# Mint_-_SCH_2025-02-01.net
KiCad netlist of a schematic drawn in EasyEDA
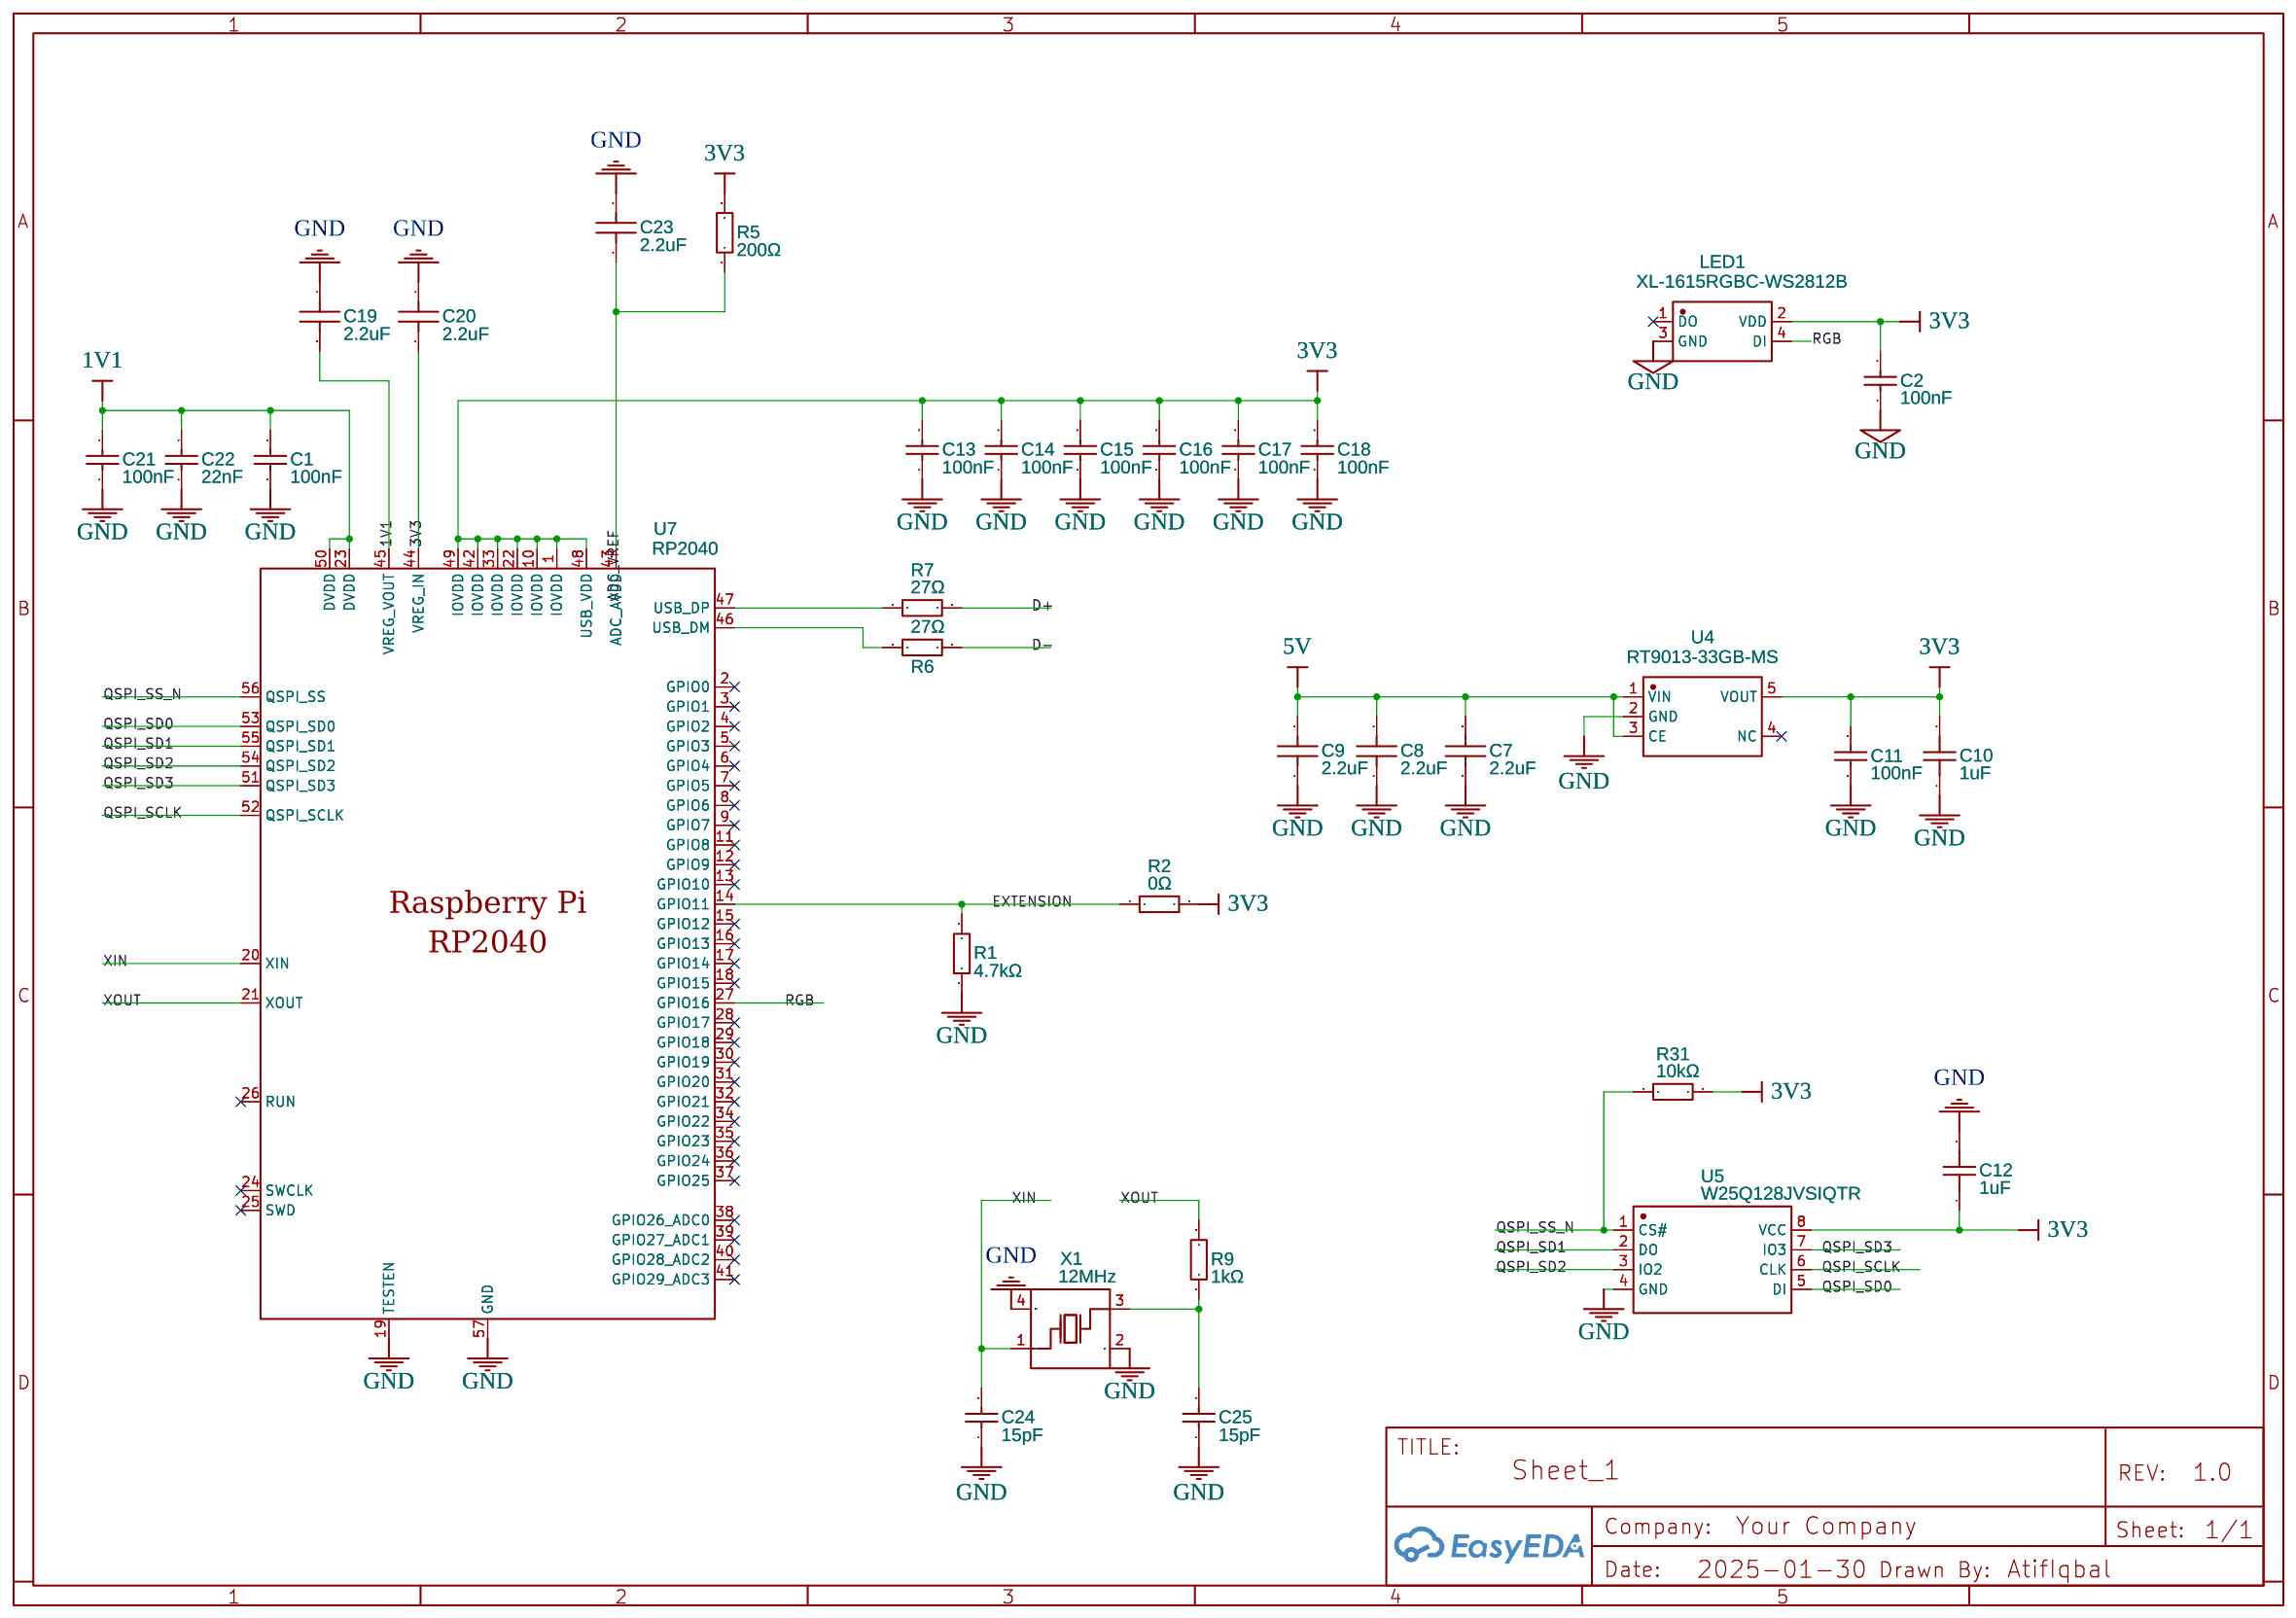
[diagram p0: schematic sheet]

(export (version "E")
  (design (tool "Eeschema 10.0.6"))
  (components
    (comp (ref "C1")
      (value "100nF")
      (fields
        (field (name "Manufacturer Part") "CL05B104KO5NNNC")
        (field (name "Manufacturer") "SAMSUNG(三星)")
      )
      (libsource (lib "") (part "CL05B104KO5NNNC"))
    )
    (comp (ref "C2")
      (value "100nF")
      (fields
        (field (name "Manufacturer Part") "CL05B104KO5NNNC")
        (field (name "Manufacturer") "SAMSUNG(三星)")
      )
      (libsource (lib "") (part "CL05B104KO5NNNC"))
    )
    (comp (ref "C7")
      (value "2.2uF")
      (fields
        (field (name "Manufacturer Part") "CL05A225MQ5NSNC")
        (field (name "Manufacturer") "SAMSUNG(三星)")
      )
      (libsource (lib "") (part "CL05A225MQ5NSNC"))
    )
    (comp (ref "C8")
      (value "2.2uF")
      (fields
        (field (name "Manufacturer Part") "CL05A225MQ5NSNC")
        (field (name "Manufacturer") "SAMSUNG(三星)")
      )
      (libsource (lib "") (part "CL05A225MQ5NSNC"))
    )
    (comp (ref "C9")
      (value "2.2uF")
      (fields
        (field (name "Manufacturer Part") "CL05A225MQ5NSNC")
        (field (name "Manufacturer") "SAMSUNG(三星)")
      )
      (libsource (lib "") (part "CL05A225MQ5NSNC"))
    )
    (comp (ref "C10")
      (value "1uF")
      (fields
        (field (name "Manufacturer Part") "CL05A105KA5NQNC")
        (field (name "Manufacturer") "SAMSUNG(三星)")
      )
      (libsource (lib "") (part "CL05A105KA5NQNC"))
    )
    (comp (ref "C11")
      (value "100nF")
      (fields
        (field (name "Manufacturer Part") "CL05B104KO5NNNC")
        (field (name "Manufacturer") "SAMSUNG(三星)")
      )
      (libsource (lib "") (part "CL05B104KO5NNNC"))
    )
    (comp (ref "C12")
      (value "1uF")
      (fields
        (field (name "Manufacturer Part") "CL05A105KA5NQNC")
        (field (name "Manufacturer") "SAMSUNG(三星)")
      )
      (libsource (lib "") (part "CL05A105KA5NQNC"))
    )
    (comp (ref "C13")
      (value "100nF")
      (fields
        (field (name "Manufacturer Part") "CL05B104KO5NNNC")
        (field (name "Manufacturer") "SAMSUNG(三星)")
      )
      (libsource (lib "") (part "CL05B104KO5NNNC"))
    )
    (comp (ref "C14")
      (value "100nF")
      (fields
        (field (name "Manufacturer Part") "CL05B104KO5NNNC")
        (field (name "Manufacturer") "SAMSUNG(三星)")
      )
      (libsource (lib "") (part "CL05B104KO5NNNC"))
    )
    (comp (ref "C15")
      (value "100nF")
      (fields
        (field (name "Manufacturer Part") "CL05B104KO5NNNC")
        (field (name "Manufacturer") "SAMSUNG(三星)")
      )
      (libsource (lib "") (part "CL05B104KO5NNNC"))
    )
    (comp (ref "C16")
      (value "100nF")
      (fields
        (field (name "Manufacturer Part") "CL05B104KO5NNNC")
        (field (name "Manufacturer") "SAMSUNG(三星)")
      )
      (libsource (lib "") (part "CL05B104KO5NNNC"))
    )
    (comp (ref "C17")
      (value "100nF")
      (fields
        (field (name "Manufacturer Part") "CL05B104KO5NNNC")
        (field (name "Manufacturer") "SAMSUNG(三星)")
      )
      (libsource (lib "") (part "CL05B104KO5NNNC"))
    )
    (comp (ref "C18")
      (value "100nF")
      (fields
        (field (name "Manufacturer Part") "CL05B104KO5NNNC")
        (field (name "Manufacturer") "SAMSUNG(三星)")
      )
      (libsource (lib "") (part "CL05B104KO5NNNC"))
    )
    (comp (ref "C19")
      (value "2.2uF")
      (fields
        (field (name "Manufacturer Part") "CL05A225MQ5NSNC")
        (field (name "Manufacturer") "SAMSUNG(三星)")
      )
      (libsource (lib "") (part "CL05A225MQ5NSNC_1"))
    )
    (comp (ref "C20")
      (value "2.2uF")
      (fields
        (field (name "Manufacturer Part") "CL05A225MQ5NSNC")
        (field (name "Manufacturer") "SAMSUNG(三星)")
      )
      (libsource (lib "") (part "CL05A225MQ5NSNC_1"))
    )
    (comp (ref "C21")
      (value "100nF")
      (fields
        (field (name "Manufacturer Part") "CL05B104KO5NNNC")
        (field (name "Manufacturer") "SAMSUNG(三星)")
      )
      (libsource (lib "") (part "CL05B104KO5NNNC"))
    )
    (comp (ref "C22")
      (value "22nF")
      (fields (field (name "Manufacturer Part") "0402B223K500NT") (field (name "Manufacturer") "FH(风华)"))
      (libsource (lib "") (part "0402B223K500NT"))
    )
    (comp (ref "C23")
      (value "2.2uF")
      (fields
        (field (name "Manufacturer Part") "CL05A225MQ5NSNC")
        (field (name "Manufacturer") "SAMSUNG(三星)")
      )
      (libsource (lib "") (part "CL05A225MQ5NSNC"))
    )
    (comp (ref "C24")
      (value "15pF")
      (fields (field (name "Manufacturer Part") "0402CG150J500NT") (field (name "Manufacturer") "FH(风华)"))
      (libsource (lib "") (part "0402CG150J500NT"))
    )
    (comp (ref "C25")
      (value "15pF")
      (fields (field (name "Manufacturer Part") "0402CG150J500NT") (field (name "Manufacturer") "FH(风华)"))
      (libsource (lib "") (part "0402CG150J500NT"))
    )
    (comp (ref "LED1")
      (value "XL-1615RGBC-WS2812B")
      (fields (field (name "Manufacturer") "XINGLIGHT(成兴光)"))
      (libsource (lib "") (part "XL-1615RGBC-WS2812B"))
    )
    (comp (ref "R1")
      (value "4.7kΩ")
      (fields
        (field (name "Manufacturer Part") "0402WGF4701TCE")
        (field (name "Manufacturer") "UNI-ROYAL(厚声)")
      )
      (libsource (lib "") (part "0402WGF4701TCE"))
    )
    (comp (ref "R2")
      (value "0Ω")
      (fields
        (field (name "Manufacturer Part") "0402WGF0000TCE")
        (field (name "Manufacturer") "UNI-ROYAL(厚声)")
      )
      (libsource (lib "") (part "0402WGF0000TCE"))
    )
    (comp (ref "R5")
      (value "200Ω")
      (fields
        (field (name "Manufacturer Part") "0402WGF2000TCE")
        (field (name "Manufacturer") "UNI-ROYAL(厚声)")
      )
      (libsource (lib "") (part "0402WGF2000TCE"))
    )
    (comp (ref "R6")
      (value "27Ω")
      (fields
        (field (name "Manufacturer Part") "0402WGJ0270TCE")
        (field (name "Manufacturer") "UNI-ROYAL(厚声)")
      )
      (libsource (lib "") (part "0402WGJ0270TCE"))
    )
    (comp (ref "R7")
      (value "27Ω")
      (fields
        (field (name "Manufacturer Part") "0402WGJ0270TCE")
        (field (name "Manufacturer") "UNI-ROYAL(厚声)")
      )
      (libsource (lib "") (part "0402WGJ0270TCE"))
    )
    (comp (ref "R9")
      (value "1kΩ")
      (fields
        (field (name "Manufacturer Part") "0402WGF1001TCE")
        (field (name "Manufacturer") "UNI-ROYAL(厚声)")
      )
      (libsource (lib "") (part "0402WGF1001TCE"))
    )
    (comp (ref "R31")
      (value "10kΩ")
      (fields (field (name "Manufacturer Part") "0402WGF1002TCE") (field (name "Manufacturer") "UniOhm"))
      (libsource (lib "") (part "0402WGF1002TCE"))
    )
    (comp (ref "U4")
      (value "RT9013-33GB-MS")
      (fields (field (name "Manufacturer") "MSKSEMI(美森科)"))
      (libsource (lib "") (part "RT9013-33GB-MS"))
    )
    (comp (ref "U5")
      (value "W25Q128JVSIQTR")
      (fields (field (name "Manufacturer Part") "W25Q128JVSIQ") (field (name "Manufacturer") "WINBOND(华邦)"))
      (libsource (lib "") (part "W25Q128JVSIQTR"))
    )
    (comp (ref "U7")
      (value "RP2040")
      (fields (field (name "Manufacturer") "Raspberry Pi(树莓派)"))
      (libsource (lib "") (part "RP2040"))
    )
    (comp (ref "X1")
      (value "12MHz")
      (fields (field (name "Manufacturer") "TAE(雅晶鑫)"))
      (libsource (lib "") (part "SMD-3225_4P12M12PF10PPM"))
    )
  )
  (nets
    (net (code "1") (name "/ADC_VREF") (class "Default")
      (node (ref "C23") (pin "1") (pinfunction "1_1") (pintype "unspecified"))
      (node (ref "R5") (pin "1") (pinfunction "1_1") (pintype "input"))
      (node (ref "U7") (pin "43") (pinfunction "ADC_AVDD_43") (pintype "bidirectional"))
    )
    (net (code "2") (name "/D+") (class "Default")
      (node (ref "R7") (pin "2") (pinfunction "2_2") (pintype "input"))
    )
    (net (code "3") (name "/D-") (class "Default")
      (node (ref "R6") (pin "2") (pinfunction "2_2") (pintype "input"))
    )
    (net (code "4") (name "/EXTENSION") (class "Default")
      (node (ref "R1") (pin "2") (pinfunction "2_2") (pintype "input"))
      (node (ref "R2") (pin "1") (pinfunction "1_1") (pintype "input"))
      (node (ref "U7") (pin "14") (pinfunction "GPIO11_14") (pintype "bidirectional"))
    )
    (net (code "5") (name "/QSPI_SCLK") (class "Default")
      (node (ref "U5") (pin "6") (pinfunction "CLK_6") (pintype "unspecified"))
      (node (ref "U7") (pin "52") (pinfunction "QSPI_SCLK_52") (pintype "output"))
    )
    (net (code "6") (name "/QSPI_SD0") (class "Default")
      (node (ref "U5") (pin "5") (pinfunction "DI_5") (pintype "unspecified"))
      (node (ref "U7") (pin "53") (pinfunction "QSPI_SD0_53") (pintype "bidirectional"))
    )
    (net (code "7") (name "/QSPI_SD1") (class "Default")
      (node (ref "U5") (pin "2") (pinfunction "DO_2") (pintype "unspecified"))
      (node (ref "U7") (pin "55") (pinfunction "QSPI_SD1_55") (pintype "bidirectional"))
    )
    (net (code "8") (name "/QSPI_SD2") (class "Default")
      (node (ref "U5") (pin "3") (pinfunction "IO2_3") (pintype "unspecified"))
      (node (ref "U7") (pin "54") (pinfunction "QSPI_SD2_54") (pintype "bidirectional"))
    )
    (net (code "9") (name "/QSPI_SD3") (class "Default")
      (node (ref "U5") (pin "7") (pinfunction "IO3_7") (pintype "unspecified"))
      (node (ref "U7") (pin "51") (pinfunction "QSPI_SD3_51") (pintype "bidirectional"))
    )
    (net (code "10") (name "/QSPI_SS_N") (class "Default")
      (node (ref "R31") (pin "1") (pinfunction "1_1") (pintype "input"))
      (node (ref "U5") (pin "1") (pinfunction "CS#_1") (pintype "unspecified"))
      (node (ref "U7") (pin "56") (pinfunction "QSPI_SS_56") (pintype "bidirectional"))
    )
    (net (code "11") (name "/RGB") (class "Default")
      (node (ref "LED1") (pin "4") (pinfunction "DI_4") (pintype "unspecified"))
      (node (ref "U7") (pin "27") (pinfunction "GPIO16_27") (pintype "bidirectional"))
    )
    (net (code "12") (name "/XIN") (class "Default")
      (node (ref "C24") (pin "2") (pinfunction "2_2") (pintype "input"))
      (node (ref "U7") (pin "20") (pinfunction "XIN_20") (pintype "input"))
      (node (ref "X1") (pin "1") (pinfunction "OSC1_1") (pintype "unspecified"))
    )
    (net (code "13") (name "/XOUT") (class "Default")
      (node (ref "R9") (pin "2") (pinfunction "2_2") (pintype "input"))
      (node (ref "U7") (pin "21") (pinfunction "XOUT_21") (pintype "unspecified"))
    )
    (net (code "14") (name "1V1") (class "Default")
      (node (ref "C1") (pin "2") (pinfunction "2_2") (pintype "input"))
      (node (ref "C19") (pin "2") (pinfunction "2_2") (pintype "unspecified"))
      (node (ref "C21") (pin "2") (pinfunction "2_2") (pintype "input"))
      (node (ref "C22") (pin "1") (pinfunction "1_1") (pintype "input"))
      (node (ref "U7") (pin "23") (pinfunction "DVDD_23") (pintype "bidirectional"))
      (node (ref "U7") (pin "45") (pinfunction "VREG_VOUT_45") (pintype "bidirectional"))
      (node (ref "U7") (pin "50") (pinfunction "DVDD_50") (pintype "bidirectional"))
    )
    (net (code "15") (name "3V3") (class "Default")
      (node (ref "C10") (pin "2") (pinfunction "2_2") (pintype "unspecified"))
      (node (ref "C11") (pin "2") (pinfunction "2_2") (pintype "input"))
      (node (ref "C12") (pin "1") (pinfunction "1_1") (pintype "unspecified"))
      (node (ref "C13") (pin "2") (pinfunction "2_2") (pintype "input"))
      (node (ref "C14") (pin "2") (pinfunction "2_2") (pintype "input"))
      (node (ref "C15") (pin "2") (pinfunction "2_2") (pintype "input"))
      (node (ref "C16") (pin "2") (pinfunction "2_2") (pintype "input"))
      (node (ref "C17") (pin "2") (pinfunction "2_2") (pintype "input"))
      (node (ref "C18") (pin "2") (pinfunction "2_2") (pintype "input"))
      (node (ref "C2") (pin "2") (pinfunction "2_2") (pintype "input"))
      (node (ref "C20") (pin "2") (pinfunction "2_2") (pintype "unspecified"))
      (node (ref "LED1") (pin "2") (pinfunction "VDD_2") (pintype "unspecified"))
      (node (ref "R2") (pin "2") (pinfunction "2_2") (pintype "input"))
      (node (ref "R31") (pin "2") (pinfunction "2_2") (pintype "input"))
      (node (ref "R5") (pin "2") (pinfunction "2_2") (pintype "input"))
      (node (ref "U4") (pin "5") (pinfunction "VOUT_5") (pintype "unspecified"))
      (node (ref "U5") (pin "8") (pinfunction "VCC_8") (pintype "unspecified"))
      (node (ref "U7") (pin "1") (pinfunction "IOVDD_1") (pintype "bidirectional"))
      (node (ref "U7") (pin "10") (pinfunction "IOVDD_10") (pintype "bidirectional"))
      (node (ref "U7") (pin "22") (pinfunction "IOVDD_22") (pintype "bidirectional"))
      (node (ref "U7") (pin "33") (pinfunction "IOVDD_33") (pintype "bidirectional"))
      (node (ref "U7") (pin "42") (pinfunction "IOVDD_42") (pintype "bidirectional"))
      (node (ref "U7") (pin "44") (pinfunction "VREG_IN_44") (pintype "bidirectional"))
      (node (ref "U7") (pin "48") (pinfunction "USB_VDD_48") (pintype "bidirectional"))
      (node (ref "U7") (pin "49") (pinfunction "IOVDD_49") (pintype "bidirectional"))
    )
    (net (code "16") (name "5V") (class "Default")
      (node (ref "C7") (pin "2") (pinfunction "2_2") (pintype "unspecified"))
      (node (ref "C8") (pin "2") (pinfunction "2_2") (pintype "unspecified"))
      (node (ref "C9") (pin "2") (pinfunction "2_2") (pintype "unspecified"))
      (node (ref "U4") (pin "1") (pinfunction "VIN_1") (pintype "unspecified"))
      (node (ref "U4") (pin "3") (pinfunction "CE_3") (pintype "unspecified"))
    )
    (net (code "17") (name "GND") (class "Default")
      (node (ref "C1") (pin "1") (pinfunction "1_1") (pintype "input"))
      (node (ref "C10") (pin "1") (pinfunction "1_1") (pintype "unspecified"))
      (node (ref "C11") (pin "1") (pinfunction "1_1") (pintype "input"))
      (node (ref "C12") (pin "2") (pinfunction "2_2") (pintype "unspecified"))
      (node (ref "C13") (pin "1") (pinfunction "1_1") (pintype "input"))
      (node (ref "C14") (pin "1") (pinfunction "1_1") (pintype "input"))
      (node (ref "C15") (pin "1") (pinfunction "1_1") (pintype "input"))
      (node (ref "C16") (pin "1") (pinfunction "1_1") (pintype "input"))
      (node (ref "C17") (pin "1") (pinfunction "1_1") (pintype "input"))
      (node (ref "C18") (pin "1") (pinfunction "1_1") (pintype "input"))
      (node (ref "C19") (pin "1") (pinfunction "1_1") (pintype "unspecified"))
      (node (ref "C2") (pin "1") (pinfunction "1_1") (pintype "input"))
      (node (ref "C20") (pin "1") (pinfunction "1_1") (pintype "unspecified"))
      (node (ref "C21") (pin "1") (pinfunction "1_1") (pintype "input"))
      (node (ref "C22") (pin "2") (pinfunction "2_2") (pintype "input"))
      (node (ref "C23") (pin "2") (pinfunction "2_2") (pintype "unspecified"))
      (node (ref "C24") (pin "1") (pinfunction "1_1") (pintype "input"))
      (node (ref "C25") (pin "1") (pinfunction "1_1") (pintype "input"))
      (node (ref "C7") (pin "1") (pinfunction "1_1") (pintype "unspecified"))
      (node (ref "C8") (pin "1") (pinfunction "1_1") (pintype "unspecified"))
      (node (ref "C9") (pin "1") (pinfunction "1_1") (pintype "unspecified"))
      (node (ref "LED1") (pin "3") (pinfunction "GND_3") (pintype "unspecified"))
      (node (ref "R1") (pin "1") (pinfunction "1_1") (pintype "input"))
      (node (ref "U4") (pin "2") (pinfunction "GND_2") (pintype "unspecified"))
      (node (ref "U5") (pin "4") (pinfunction "GND_4") (pintype "unspecified"))
      (node (ref "U7") (pin "19") (pinfunction "TESTEN_19") (pintype "unspecified"))
      (node (ref "U7") (pin "57") (pinfunction "GND_57") (pintype "bidirectional"))
      (node (ref "X1") (pin "2") (pinfunction "GND_2") (pintype "unspecified"))
      (node (ref "X1") (pin "4") (pinfunction "GND_4") (pintype "unspecified"))
    )
    (net (code "18") (name "Net-(U7-USB_DM)") (class "Default")
      (node (ref "R6") (pin "1") (pinfunction "1_1") (pintype "input"))
      (node (ref "U7") (pin "46") (pinfunction "USB_DM_46") (pintype "bidirectional"))
    )
    (net (code "19") (name "Net-(U7-USB_DP)") (class "Default")
      (node (ref "R7") (pin "1") (pinfunction "1_1") (pintype "input"))
      (node (ref "U7") (pin "47") (pinfunction "USB_DP_47") (pintype "bidirectional"))
    )
    (net (code "20") (name "Net-(X1-OSC2)") (class "Default")
      (node (ref "C25") (pin "2") (pinfunction "2_2") (pintype "input"))
      (node (ref "R9") (pin "1") (pinfunction "1_1") (pintype "input"))
      (node (ref "X1") (pin "3") (pinfunction "OSC2_3") (pintype "unspecified"))
    )
    (net (code "21") (name "unconnected-(LED1-DO-Pad1)") (class "Default")
      (node (ref "LED1") (pin "1") (pinfunction "DO_1") (pintype "unspecified+no_connect"))
    )
    (net (code "22") (name "unconnected-(U4-NC-Pad4)") (class "Default")
      (node (ref "U4") (pin "4") (pinfunction "NC_4") (pintype "unspecified+no_connect"))
    )
    (net (code "23") (name "unconnected-(U7-GPIO0-Pad2)") (class "Default")
      (node (ref "U7") (pin "2") (pinfunction "GPIO0_2") (pintype "bidirectional+no_connect"))
    )
    (net (code "24") (name "unconnected-(U7-GPIO1-Pad3)") (class "Default")
      (node (ref "U7") (pin "3") (pinfunction "GPIO1_3") (pintype "bidirectional+no_connect"))
    )
    (net (code "25") (name "unconnected-(U7-GPIO2-Pad4)") (class "Default")
      (node (ref "U7") (pin "4") (pinfunction "GPIO2_4") (pintype "bidirectional+no_connect"))
    )
    (net (code "26") (name "unconnected-(U7-GPIO3-Pad5)") (class "Default")
      (node (ref "U7") (pin "5") (pinfunction "GPIO3_5") (pintype "bidirectional+no_connect"))
    )
    (net (code "27") (name "unconnected-(U7-GPIO4-Pad6)") (class "Default")
      (node (ref "U7") (pin "6") (pinfunction "GPIO4_6") (pintype "bidirectional+no_connect"))
    )
    (net (code "28") (name "unconnected-(U7-GPIO5-Pad7)") (class "Default")
      (node (ref "U7") (pin "7") (pinfunction "GPIO5_7") (pintype "bidirectional+no_connect"))
    )
    (net (code "29") (name "unconnected-(U7-GPIO6-Pad8)") (class "Default")
      (node (ref "U7") (pin "8") (pinfunction "GPIO6_8") (pintype "bidirectional+no_connect"))
    )
    (net (code "30") (name "unconnected-(U7-GPIO7-Pad9)") (class "Default")
      (node (ref "U7") (pin "9") (pinfunction "GPIO7_9") (pintype "bidirectional+no_connect"))
    )
    (net (code "31") (name "unconnected-(U7-GPIO8-Pad11)") (class "Default")
      (node (ref "U7") (pin "11") (pinfunction "GPIO8_11") (pintype "bidirectional+no_connect"))
    )
    (net (code "32") (name "unconnected-(U7-GPIO9-Pad12)") (class "Default")
      (node (ref "U7") (pin "12") (pinfunction "GPIO9_12") (pintype "bidirectional+no_connect"))
    )
    (net (code "33") (name "unconnected-(U7-GPIO10-Pad13)") (class "Default")
      (node (ref "U7") (pin "13") (pinfunction "GPIO10_13") (pintype "bidirectional+no_connect"))
    )
    (net (code "34") (name "unconnected-(U7-GPIO12-Pad15)") (class "Default")
      (node (ref "U7") (pin "15") (pinfunction "GPIO12_15") (pintype "bidirectional+no_connect"))
    )
    (net (code "35") (name "unconnected-(U7-GPIO13-Pad16)") (class "Default")
      (node (ref "U7") (pin "16") (pinfunction "GPIO13_16") (pintype "bidirectional+no_connect"))
    )
    (net (code "36") (name "unconnected-(U7-GPIO14-Pad17)") (class "Default")
      (node (ref "U7") (pin "17") (pinfunction "GPIO14_17") (pintype "bidirectional+no_connect"))
    )
    (net (code "37") (name "unconnected-(U7-GPIO15-Pad18)") (class "Default")
      (node (ref "U7") (pin "18") (pinfunction "GPIO15_18") (pintype "bidirectional+no_connect"))
    )
    (net (code "38") (name "unconnected-(U7-GPIO17-Pad28)") (class "Default")
      (node (ref "U7") (pin "28") (pinfunction "GPIO17_28") (pintype "bidirectional+no_connect"))
    )
    (net (code "39") (name "unconnected-(U7-GPIO18-Pad29)") (class "Default")
      (node (ref "U7") (pin "29") (pinfunction "GPIO18_29") (pintype "bidirectional+no_connect"))
    )
    (net (code "40") (name "unconnected-(U7-GPIO19-Pad30)") (class "Default")
      (node (ref "U7") (pin "30") (pinfunction "GPIO19_30") (pintype "bidirectional+no_connect"))
    )
    (net (code "41") (name "unconnected-(U7-GPIO20-Pad31)") (class "Default")
      (node (ref "U7") (pin "31") (pinfunction "GPIO20_31") (pintype "bidirectional+no_connect"))
    )
    (net (code "42") (name "unconnected-(U7-GPIO21-Pad32)") (class "Default")
      (node (ref "U7") (pin "32") (pinfunction "GPIO21_32") (pintype "bidirectional+no_connect"))
    )
    (net (code "43") (name "unconnected-(U7-GPIO22-Pad34)") (class "Default")
      (node (ref "U7") (pin "34") (pinfunction "GPIO22_34") (pintype "bidirectional+no_connect"))
    )
    (net (code "44") (name "unconnected-(U7-GPIO23-Pad35)") (class "Default")
      (node (ref "U7") (pin "35") (pinfunction "GPIO23_35") (pintype "bidirectional+no_connect"))
    )
    (net (code "45") (name "unconnected-(U7-GPIO24-Pad36)") (class "Default")
      (node (ref "U7") (pin "36") (pinfunction "GPIO24_36") (pintype "bidirectional+no_connect"))
    )
    (net (code "46") (name "unconnected-(U7-GPIO25-Pad37)") (class "Default")
      (node (ref "U7") (pin "37") (pinfunction "GPIO25_37") (pintype "bidirectional+no_connect"))
    )
    (net (code "47") (name "unconnected-(U7-GPIO26_ADC0-Pad38)") (class "Default")
      (node (ref "U7") (pin "38") (pinfunction "GPIO26_ADC0_38") (pintype "bidirectional+no_connect"))
    )
    (net (code "48") (name "unconnected-(U7-GPIO27_ADC1-Pad39)") (class "Default")
      (node (ref "U7") (pin "39") (pinfunction "GPIO27_ADC1_39") (pintype "bidirectional+no_connect"))
    )
    (net (code "49") (name "unconnected-(U7-GPIO28_ADC2-Pad40)") (class "Default")
      (node (ref "U7") (pin "40") (pinfunction "GPIO28_ADC2_40") (pintype "bidirectional+no_connect"))
    )
    (net (code "50") (name "unconnected-(U7-GPIO29_ADC3-Pad41)") (class "Default")
      (node (ref "U7") (pin "41") (pinfunction "GPIO29_ADC3_41") (pintype "bidirectional+no_connect"))
    )
    (net (code "51") (name "unconnected-(U7-RUN-Pad26)") (class "Default")
      (node (ref "U7") (pin "26") (pinfunction "RUN_26") (pintype "input+no_connect"))
    )
    (net (code "52") (name "unconnected-(U7-SWCLK-Pad24)") (class "Default")
      (node (ref "U7") (pin "24") (pinfunction "SWCLK_24") (pintype "output+no_connect"))
    )
    (net (code "53") (name "unconnected-(U7-SWD-Pad25)") (class "Default")
      (node (ref "U7") (pin "25") (pinfunction "SWD_25") (pintype "bidirectional+no_connect"))
    )
  )
)
